# sercon.net
KiCad netlist of a schematic drawn in EAGLE
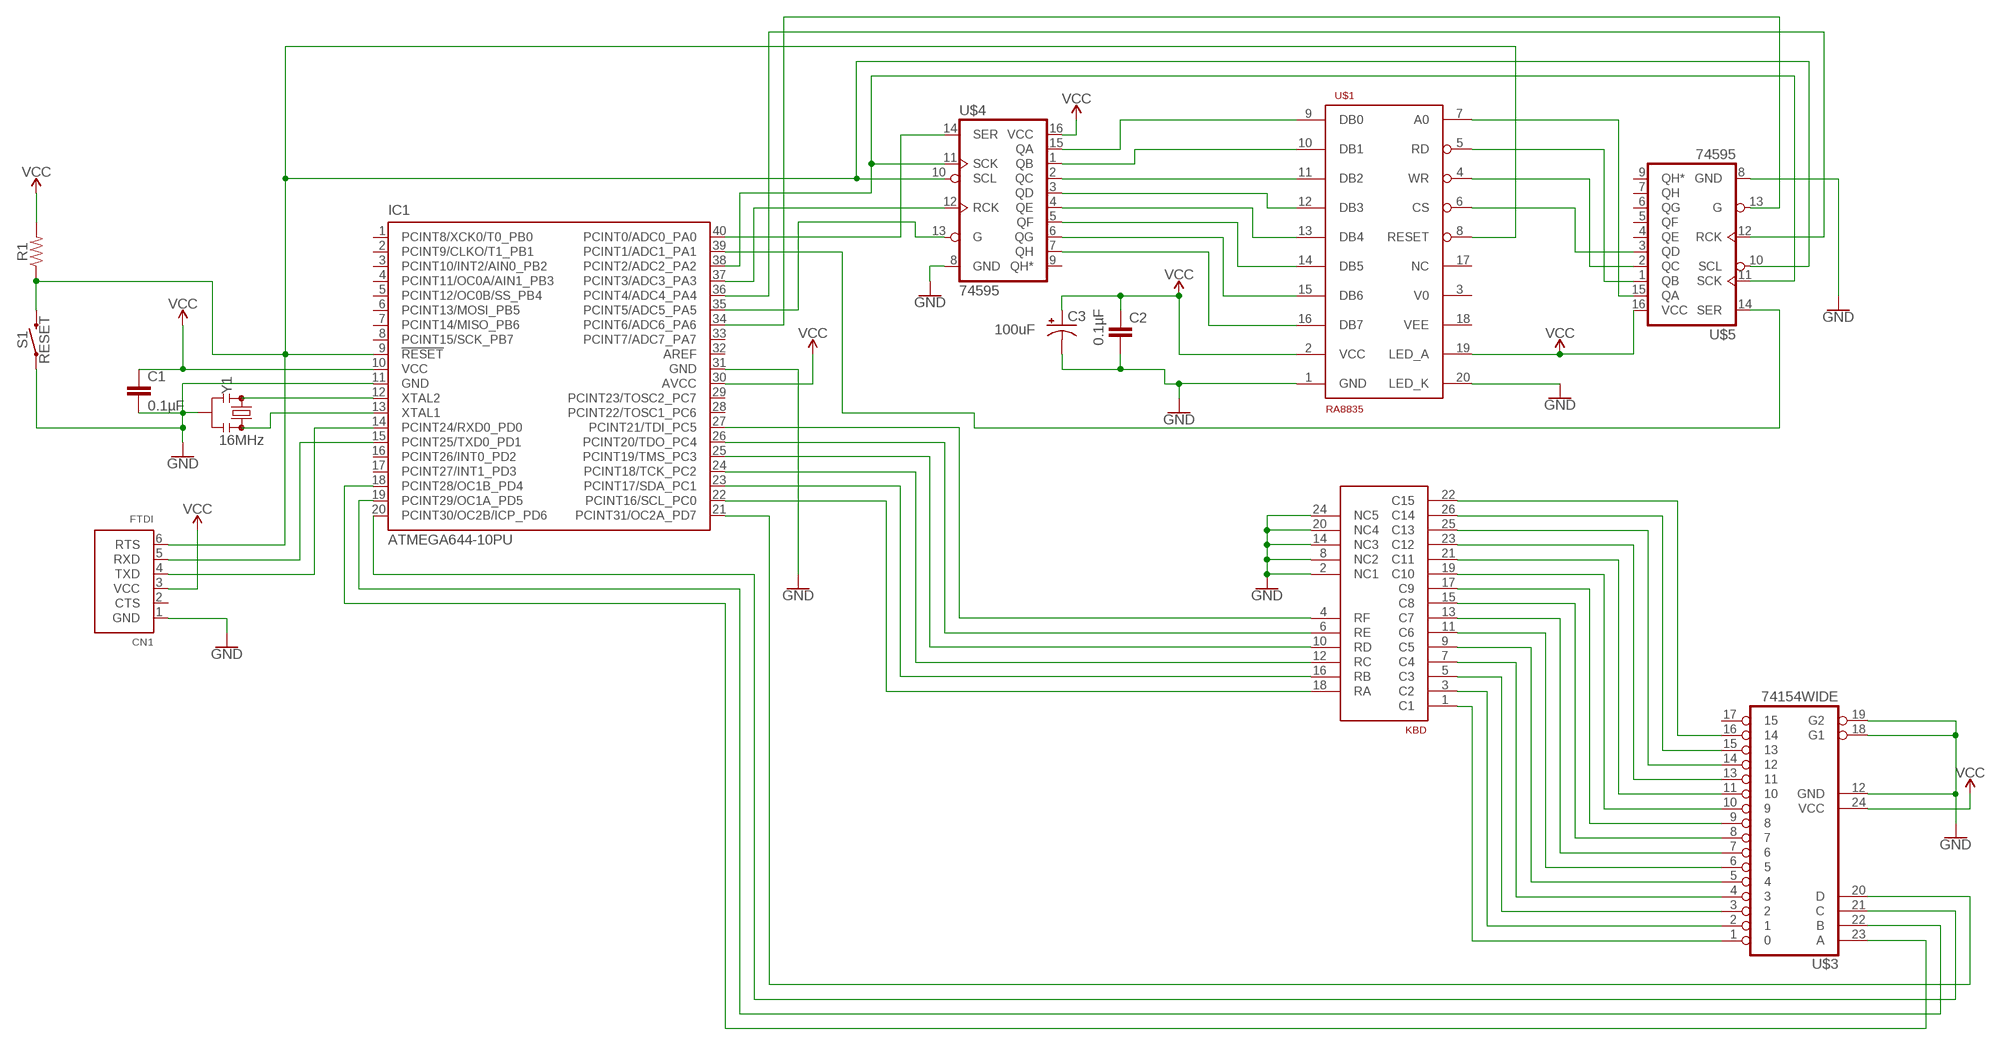
[diagram p0: schematic, sheet 1]

(export (version "E")
  (design (tool "Eeschema 10.0.6"))
  (components
    (comp (ref "C1")
      (value "0.1µF")
      (footprint "eagle-import:C2.5-3")
      (libsource (lib "eagle-import") (part "C2,5-3"))
    )
    (comp (ref "C2")
      (value "0.1µF")
      (footprint "eagle-import:C2.5-3")
      (libsource (lib "eagle-import") (part "C2,5-3"))
    )
    (comp (ref "C3")
      (value "100uF")
      (footprint "eagle-import:CPOL-RADIAL-2.5MM-6.5MM")
      (libsource (lib "eagle-import") (part "100UF-POLAR-RADIAL-2.5MM-25V-20%"))
    )
    (comp (ref "CN1")
      (value "FTDI")
      (footprint "eagle-import:1X06_ROUND")
      (libsource (lib "eagle-import") (part "FTDIUSBCABLE"))
    )
    (comp (ref "IC1")
      (value "ATMEGA644-10PU")
      (footprint "eagle-import:DIL40")
      (fields (field (name "MPN") "ATMEGA644V-10PU"))
      (libsource (lib "eagle-import") (part "ATMEGA644-PU10"))
    )
    (comp (ref "R1")
      (value "RESISTORAXIAL-0.3")
      (footprint "eagle-import:AXIAL-0.3")
      (libsource (lib "eagle-import") (part "RESISTORAXIAL-0.3"))
    )
    (comp (ref "S1")
      (value "RESET")
      (footprint "eagle-import:TACTILE_SWITCH_PTH_6.0MM")
      (libsource (lib "eagle-import") (part "MOMENTARY-SWITCH-SPST-PTH-6.0MM"))
    )
    (comp (ref "U$1")
      (value "RA8835")
      (footprint "eagle-import:2X10")
      (libsource (lib "eagle-import") (part "RA8835"))
    )
    (comp (ref "U$2")
      (value "5140KBD")
      (footprint "eagle-import:2X13")
      (libsource (lib "eagle-import") (part "5140KBD"))
    )
    (comp (ref "U$3")
      (value "74154WIDE")
      (footprint "eagle-import:DIL24-6")
      (libsource (lib "eagle-import") (part "74154WIDE"))
    )
    (comp (ref "U$4")
      (value "74595")
      (footprint "eagle-import:DIL16")
      (libsource (lib "eagle-import") (part "74595"))
    )
    (comp (ref "U$5")
      (value "74595")
      (footprint "eagle-import:DIL16")
      (libsource (lib "eagle-import") (part "74595"))
    )
    (comp (ref "Y1")
      (value "16MHz")
      (footprint "eagle-import:RESONATOR-PTH-7.6X3.8")
      (libsource (lib "eagle-import") (part "RESONATORPTH-7.6X3.8"))
    )
  )
  (nets
    (net (code "1") (name "GND") (class "Default")
      (node (ref "C1") (pin "2") (pinfunction "2_2") (pintype "passive"))
      (node (ref "C2") (pin "2") (pinfunction "2_2") (pintype "passive"))
      (node (ref "C3") (pin "2") (pinfunction "-_2") (pintype "passive"))
      (node (ref "CN1") (pin "1") (pinfunction "GND_1") (pintype "bidirectional"))
      (node (ref "IC1") (pin "11") (pinfunction "GND_11") (pintype "power_in"))
      (node (ref "IC1") (pin "31") (pinfunction "GND_31") (pintype "power_in"))
      (node (ref "S1") (pin "1") (pinfunction "1_1") (pintype "passive"))
      (node (ref "U$1") (pin "1") (pinfunction "GND_1") (pintype "power_in"))
      (node (ref "U$1") (pin "20") (pinfunction "LED_K_20") (pintype "bidirectional"))
      (node (ref "U$2") (pin "14") (pinfunction "NC3_14") (pintype "bidirectional"))
      (node (ref "U$2") (pin "2") (pinfunction "NC1_2") (pintype "bidirectional"))
      (node (ref "U$2") (pin "20") (pinfunction "NC4_20") (pintype "bidirectional"))
      (node (ref "U$2") (pin "24") (pinfunction "NC5_24") (pintype "bidirectional"))
      (node (ref "U$2") (pin "8") (pinfunction "NC2_8") (pintype "bidirectional"))
      (node (ref "U$3") (pin "12") (pinfunction "GND_12") (pintype "power_in"))
      (node (ref "U$3") (pin "18") (pinfunction "G1_18") (pintype "input"))
      (node (ref "U$3") (pin "19") (pinfunction "G2_19") (pintype "input"))
      (node (ref "U$4") (pin "8") (pinfunction "GND_8") (pintype "power_in"))
      (node (ref "U$5") (pin "8") (pinfunction "GND_8") (pintype "power_in"))
      (node (ref "Y1") (pin "2") (pinfunction "2_2") (pintype "passive"))
    )
    (net (code "2") (name "Net-(CN1-RTS)") (class "Default")
      (node (ref "CN1") (pin "6") (pinfunction "RTS_6") (pintype "bidirectional"))
      (node (ref "IC1") (pin "9") (pinfunction "~{RESET}_9") (pintype "input"))
      (node (ref "R1") (pin "P$1") (pinfunction "1_P$1") (pintype "passive"))
      (node (ref "S1") (pin "3") (pinfunction "2_3") (pintype "passive"))
      (node (ref "U$1") (pin "8") (pinfunction "RESET_8") (pintype "input"))
      (node (ref "U$4") (pin "10") (pinfunction "SCL_10") (pintype "input"))
      (node (ref "U$5") (pin "10") (pinfunction "SCL_10") (pintype "input"))
    )
    (net (code "3") (name "Net-(CN1-RXD)") (class "Default")
      (node (ref "CN1") (pin "5") (pinfunction "RXD_5") (pintype "bidirectional"))
      (node (ref "IC1") (pin "15") (pinfunction "PCINT25/TXD0_PD1_15") (pintype "bidirectional"))
    )
    (net (code "4") (name "Net-(CN1-TXD)") (class "Default")
      (node (ref "CN1") (pin "4") (pinfunction "TXD_4") (pintype "bidirectional"))
      (node (ref "IC1") (pin "14") (pinfunction "PCINT24/RXD0_PD0_14") (pintype "bidirectional"))
    )
    (net (code "5") (name "Net-(IC1-PCINT0{slash}ADC0_PA0)") (class "Default")
      (node (ref "IC1") (pin "40") (pinfunction "PCINT0/ADC0_PA0_40") (pintype "bidirectional"))
      (node (ref "U$4") (pin "14") (pinfunction "SER_14") (pintype "input"))
    )
    (net (code "6") (name "Net-(IC1-PCINT1{slash}ADC1_PA1)") (class "Default")
      (node (ref "IC1") (pin "39") (pinfunction "PCINT1/ADC1_PA1_39") (pintype "bidirectional"))
      (node (ref "U$5") (pin "14") (pinfunction "SER_14") (pintype "input"))
    )
    (net (code "7") (name "Net-(IC1-PCINT2{slash}ADC2_PA2)") (class "Default")
      (node (ref "IC1") (pin "38") (pinfunction "PCINT2/ADC2_PA2_38") (pintype "bidirectional"))
      (node (ref "U$4") (pin "11") (pinfunction "SCK_11") (pintype "input"))
      (node (ref "U$5") (pin "11") (pinfunction "SCK_11") (pintype "input"))
    )
    (net (code "8") (name "Net-(IC1-PCINT3{slash}ADC3_PA3)") (class "Default")
      (node (ref "IC1") (pin "37") (pinfunction "PCINT3/ADC3_PA3_37") (pintype "bidirectional"))
      (node (ref "U$4") (pin "12") (pinfunction "RCK_12") (pintype "input"))
    )
    (net (code "9") (name "Net-(IC1-PCINT4{slash}ADC4_PA4)") (class "Default")
      (node (ref "IC1") (pin "36") (pinfunction "PCINT4/ADC4_PA4_36") (pintype "bidirectional"))
      (node (ref "U$5") (pin "12") (pinfunction "RCK_12") (pintype "input"))
    )
    (net (code "10") (name "Net-(IC1-PCINT5{slash}ADC5_PA5)") (class "Default")
      (node (ref "IC1") (pin "35") (pinfunction "PCINT5/ADC5_PA5_35") (pintype "bidirectional"))
      (node (ref "U$4") (pin "13") (pinfunction "G_13") (pintype "input"))
    )
    (net (code "11") (name "Net-(IC1-PCINT6{slash}ADC6_PA6)") (class "Default")
      (node (ref "IC1") (pin "34") (pinfunction "PCINT6/ADC6_PA6_34") (pintype "bidirectional"))
      (node (ref "U$5") (pin "13") (pinfunction "G_13") (pintype "input"))
    )
    (net (code "12") (name "Net-(IC1-PCINT16{slash}SCL_PC0)") (class "Default")
      (node (ref "IC1") (pin "22") (pinfunction "PCINT16/SCL_PC0_22") (pintype "bidirectional"))
      (node (ref "U$2") (pin "18") (pinfunction "RA_18") (pintype "bidirectional"))
    )
    (net (code "13") (name "Net-(IC1-PCINT17{slash}SDA_PC1)") (class "Default")
      (node (ref "IC1") (pin "23") (pinfunction "PCINT17/SDA_PC1_23") (pintype "bidirectional"))
      (node (ref "U$2") (pin "16") (pinfunction "RB_16") (pintype "bidirectional"))
    )
    (net (code "14") (name "Net-(IC1-PCINT18{slash}TCK_PC2)") (class "Default")
      (node (ref "IC1") (pin "24") (pinfunction "PCINT18/TCK_PC2_24") (pintype "bidirectional"))
      (node (ref "U$2") (pin "12") (pinfunction "RC_12") (pintype "bidirectional"))
    )
    (net (code "15") (name "Net-(IC1-PCINT19{slash}TMS_PC3)") (class "Default")
      (node (ref "IC1") (pin "25") (pinfunction "PCINT19/TMS_PC3_25") (pintype "bidirectional"))
      (node (ref "U$2") (pin "10") (pinfunction "RD_10") (pintype "bidirectional"))
    )
    (net (code "16") (name "Net-(IC1-PCINT20{slash}TDO_PC4)") (class "Default")
      (node (ref "IC1") (pin "26") (pinfunction "PCINT20/TDO_PC4_26") (pintype "bidirectional"))
      (node (ref "U$2") (pin "6") (pinfunction "RE_6") (pintype "bidirectional"))
    )
    (net (code "17") (name "Net-(IC1-PCINT21{slash}TDI_PC5)") (class "Default")
      (node (ref "IC1") (pin "27") (pinfunction "PCINT21/TDI_PC5_27") (pintype "bidirectional"))
      (node (ref "U$2") (pin "4") (pinfunction "RF_4") (pintype "bidirectional"))
    )
    (net (code "18") (name "Net-(IC1-PCINT28{slash}OC1B_PD4)") (class "Default")
      (node (ref "IC1") (pin "18") (pinfunction "PCINT28/OC1B_PD4_18") (pintype "bidirectional"))
      (node (ref "U$3") (pin "23") (pinfunction "A_23") (pintype "input"))
    )
    (net (code "19") (name "Net-(IC1-PCINT29{slash}OC1A_PD5)") (class "Default")
      (node (ref "IC1") (pin "19") (pinfunction "PCINT29/OC1A_PD5_19") (pintype "bidirectional"))
      (node (ref "U$3") (pin "22") (pinfunction "B_22") (pintype "input"))
    )
    (net (code "20") (name "Net-(IC1-PCINT30{slash}OC2B{slash}ICP_PD6)") (class "Default")
      (node (ref "IC1") (pin "20") (pinfunction "PCINT30/OC2B/ICP_PD6_20") (pintype "bidirectional"))
      (node (ref "U$3") (pin "21") (pinfunction "C_21") (pintype "input"))
    )
    (net (code "21") (name "Net-(IC1-PCINT31{slash}OC2A_PD7)") (class "Default")
      (node (ref "IC1") (pin "21") (pinfunction "PCINT31/OC2A_PD7_21") (pintype "bidirectional"))
      (node (ref "U$3") (pin "20") (pinfunction "D_20") (pintype "input"))
    )
    (net (code "22") (name "Net-(IC1-XTAL1)") (class "Default")
      (node (ref "IC1") (pin "13") (pinfunction "XTAL1_13") (pintype "input"))
      (node (ref "Y1") (pin "3") (pinfunction "3_3") (pintype "passive"))
    )
    (net (code "23") (name "Net-(IC1-XTAL2)") (class "Default")
      (node (ref "IC1") (pin "12") (pinfunction "XTAL2_12") (pintype "output"))
      (node (ref "Y1") (pin "1") (pinfunction "1_1") (pintype "passive"))
    )
    (net (code "24") (name "Net-(U$1-A0)") (class "Default")
      (node (ref "U$1") (pin "7") (pinfunction "A0_7") (pintype "input"))
      (node (ref "U$5") (pin "15") (pinfunction "QA_15") (pintype "tri_state"))
    )
    (net (code "25") (name "Net-(U$1-CS)") (class "Default")
      (node (ref "U$1") (pin "6") (pinfunction "CS_6") (pintype "input"))
      (node (ref "U$5") (pin "3") (pinfunction "QD_3") (pintype "tri_state"))
    )
    (net (code "26") (name "Net-(U$1-DB0)") (class "Default")
      (node (ref "U$1") (pin "9") (pinfunction "DB0_9") (pintype "bidirectional"))
      (node (ref "U$4") (pin "15") (pinfunction "QA_15") (pintype "tri_state"))
    )
    (net (code "27") (name "Net-(U$1-DB1)") (class "Default")
      (node (ref "U$1") (pin "10") (pinfunction "DB1_10") (pintype "bidirectional"))
      (node (ref "U$4") (pin "1") (pinfunction "QB_1") (pintype "tri_state"))
    )
    (net (code "28") (name "Net-(U$1-DB2)") (class "Default")
      (node (ref "U$1") (pin "11") (pinfunction "DB2_11") (pintype "bidirectional"))
      (node (ref "U$4") (pin "2") (pinfunction "QC_2") (pintype "tri_state"))
    )
    (net (code "29") (name "Net-(U$1-DB3)") (class "Default")
      (node (ref "U$1") (pin "12") (pinfunction "DB3_12") (pintype "bidirectional"))
      (node (ref "U$4") (pin "3") (pinfunction "QD_3") (pintype "tri_state"))
    )
    (net (code "30") (name "Net-(U$1-DB4)") (class "Default")
      (node (ref "U$1") (pin "13") (pinfunction "DB4_13") (pintype "bidirectional"))
      (node (ref "U$4") (pin "4") (pinfunction "QE_4") (pintype "tri_state"))
    )
    (net (code "31") (name "Net-(U$1-DB5)") (class "Default")
      (node (ref "U$1") (pin "14") (pinfunction "DB5_14") (pintype "bidirectional"))
      (node (ref "U$4") (pin "5") (pinfunction "QF_5") (pintype "tri_state"))
    )
    (net (code "32") (name "Net-(U$1-DB6)") (class "Default")
      (node (ref "U$1") (pin "15") (pinfunction "DB6_15") (pintype "bidirectional"))
      (node (ref "U$4") (pin "6") (pinfunction "QG_6") (pintype "tri_state"))
    )
    (net (code "33") (name "Net-(U$1-DB7)") (class "Default")
      (node (ref "U$1") (pin "16") (pinfunction "DB7_16") (pintype "bidirectional"))
      (node (ref "U$4") (pin "7") (pinfunction "QH_7") (pintype "tri_state"))
    )
    (net (code "34") (name "Net-(U$1-RD)") (class "Default")
      (node (ref "U$1") (pin "5") (pinfunction "RD_5") (pintype "input"))
      (node (ref "U$5") (pin "1") (pinfunction "QB_1") (pintype "tri_state"))
    )
    (net (code "35") (name "Net-(U$1-WR)") (class "Default")
      (node (ref "U$1") (pin "4") (pinfunction "WR_4") (pintype "input"))
      (node (ref "U$5") (pin "2") (pinfunction "QC_2") (pintype "tri_state"))
    )
    (net (code "36") (name "Net-(U$2-C1)") (class "Default")
      (node (ref "U$2") (pin "1") (pinfunction "C1_1") (pintype "bidirectional"))
      (node (ref "U$3") (pin "1") (pinfunction "0_1") (pintype "output"))
    )
    (net (code "37") (name "Net-(U$2-C2)") (class "Default")
      (node (ref "U$2") (pin "3") (pinfunction "C2_3") (pintype "bidirectional"))
      (node (ref "U$3") (pin "2") (pinfunction "1_2") (pintype "output"))
    )
    (net (code "38") (name "Net-(U$2-C3)") (class "Default")
      (node (ref "U$2") (pin "5") (pinfunction "C3_5") (pintype "bidirectional"))
      (node (ref "U$3") (pin "3") (pinfunction "2_3") (pintype "output"))
    )
    (net (code "39") (name "Net-(U$2-C4)") (class "Default")
      (node (ref "U$2") (pin "7") (pinfunction "C4_7") (pintype "bidirectional"))
      (node (ref "U$3") (pin "4") (pinfunction "3_4") (pintype "output"))
    )
    (net (code "40") (name "Net-(U$2-C5)") (class "Default")
      (node (ref "U$2") (pin "9") (pinfunction "C5_9") (pintype "bidirectional"))
      (node (ref "U$3") (pin "5") (pinfunction "4_5") (pintype "output"))
    )
    (net (code "41") (name "Net-(U$2-C6)") (class "Default")
      (node (ref "U$2") (pin "11") (pinfunction "C6_11") (pintype "bidirectional"))
      (node (ref "U$3") (pin "6") (pinfunction "5_6") (pintype "output"))
    )
    (net (code "42") (name "Net-(U$2-C7)") (class "Default")
      (node (ref "U$2") (pin "13") (pinfunction "C7_13") (pintype "bidirectional"))
      (node (ref "U$3") (pin "7") (pinfunction "6_7") (pintype "output"))
    )
    (net (code "43") (name "Net-(U$2-C8)") (class "Default")
      (node (ref "U$2") (pin "15") (pinfunction "C8_15") (pintype "bidirectional"))
      (node (ref "U$3") (pin "8") (pinfunction "7_8") (pintype "output"))
    )
    (net (code "44") (name "Net-(U$2-C9)") (class "Default")
      (node (ref "U$2") (pin "17") (pinfunction "C9_17") (pintype "bidirectional"))
      (node (ref "U$3") (pin "9") (pinfunction "8_9") (pintype "output"))
    )
    (net (code "45") (name "Net-(U$2-C10)") (class "Default")
      (node (ref "U$2") (pin "19") (pinfunction "C10_19") (pintype "bidirectional"))
      (node (ref "U$3") (pin "10") (pinfunction "9_10") (pintype "output"))
    )
    (net (code "46") (name "Net-(U$2-C11)") (class "Default")
      (node (ref "U$2") (pin "21") (pinfunction "C11_21") (pintype "bidirectional"))
      (node (ref "U$3") (pin "11") (pinfunction "10_11") (pintype "output"))
    )
    (net (code "47") (name "Net-(U$2-C12)") (class "Default")
      (node (ref "U$2") (pin "23") (pinfunction "C12_23") (pintype "bidirectional"))
      (node (ref "U$3") (pin "13") (pinfunction "11_13") (pintype "output"))
    )
    (net (code "48") (name "Net-(U$2-C13)") (class "Default")
      (node (ref "U$2") (pin "25") (pinfunction "C13_25") (pintype "bidirectional"))
      (node (ref "U$3") (pin "14") (pinfunction "12_14") (pintype "output"))
    )
    (net (code "49") (name "Net-(U$2-C14)") (class "Default")
      (node (ref "U$2") (pin "26") (pinfunction "C14_26") (pintype "bidirectional"))
      (node (ref "U$3") (pin "15") (pinfunction "13_15") (pintype "output"))
    )
    (net (code "50") (name "Net-(U$2-C15)") (class "Default")
      (node (ref "U$2") (pin "22") (pinfunction "C15_22") (pintype "bidirectional"))
      (node (ref "U$3") (pin "16") (pinfunction "14_16") (pintype "output"))
    )
    (net (code "51") (name "VCC") (class "Default")
      (node (ref "C1") (pin "1") (pinfunction "1_1") (pintype "passive"))
      (node (ref "C2") (pin "1") (pinfunction "1_1") (pintype "passive"))
      (node (ref "C3") (pin "1") (pinfunction "+_1") (pintype "passive"))
      (node (ref "CN1") (pin "3") (pinfunction "VCC_3") (pintype "bidirectional"))
      (node (ref "IC1") (pin "10") (pinfunction "VCC_10") (pintype "power_in"))
      (node (ref "IC1") (pin "30") (pinfunction "AVCC_30") (pintype "power_in"))
      (node (ref "R1") (pin "P$2") (pinfunction "2_P$2") (pintype "passive"))
      (node (ref "U$1") (pin "19") (pinfunction "LED_A_19") (pintype "bidirectional"))
      (node (ref "U$1") (pin "2") (pinfunction "VCC_2") (pintype "power_in"))
      (node (ref "U$3") (pin "24") (pinfunction "VCC_24") (pintype "power_in"))
      (node (ref "U$4") (pin "16") (pinfunction "VCC_16") (pintype "power_in"))
      (node (ref "U$5") (pin "16") (pinfunction "VCC_16") (pintype "power_in"))
    )
    (net (code "52") (name "unconnected-(CN1-CTS-Pad2)") (class "Default")
      (node (ref "CN1") (pin "2") (pinfunction "CTS_2") (pintype "bidirectional"))
    )
    (net (code "53") (name "unconnected-(IC1-AREF-Pad32)") (class "Default")
      (node (ref "IC1") (pin "32") (pinfunction "AREF_32") (pintype "passive"))
    )
    (net (code "54") (name "unconnected-(IC1-PCINT7{slash}ADC7_PA7-Pad33)") (class "Default")
      (node (ref "IC1") (pin "33") (pinfunction "PCINT7/ADC7_PA7_33") (pintype "bidirectional"))
    )
    (net (code "55") (name "unconnected-(IC1-PCINT8{slash}XCK0{slash}T0_PB0-Pad1)") (class "Default")
      (node (ref "IC1") (pin "1") (pinfunction "PCINT8/XCK0/T0_PB0_1") (pintype "bidirectional"))
    )
    (net (code "56") (name "unconnected-(IC1-PCINT9{slash}CLKO{slash}T1_PB1-Pad2)") (class "Default")
      (node (ref "IC1") (pin "2") (pinfunction "PCINT9/CLKO/T1_PB1_2") (pintype "bidirectional"))
    )
    (net (code "57") (name "unconnected-(IC1-PCINT10{slash}INT2{slash}AIN0_PB2-Pad3)") (class "Default")
      (node (ref "IC1") (pin "3") (pinfunction "PCINT10/INT2/AIN0_PB2_3") (pintype "bidirectional"))
    )
    (net (code "58") (name "unconnected-(IC1-PCINT11{slash}OC0A{slash}AIN1_PB3-Pad4)") (class "Default")
      (node (ref "IC1") (pin "4") (pinfunction "PCINT11/OC0A/AIN1_PB3_4") (pintype "bidirectional"))
    )
    (net (code "59") (name "unconnected-(IC1-PCINT12{slash}OC0B{slash}SS_PB4-Pad5)") (class "Default")
      (node (ref "IC1") (pin "5") (pinfunction "PCINT12/OC0B/SS_PB4_5") (pintype "bidirectional"))
    )
    (net (code "60") (name "unconnected-(IC1-PCINT13{slash}MOSI_PB5-Pad6)") (class "Default")
      (node (ref "IC1") (pin "6") (pinfunction "PCINT13/MOSI_PB5_6") (pintype "bidirectional"))
    )
    (net (code "61") (name "unconnected-(IC1-PCINT14{slash}MISO_PB6-Pad7)") (class "Default")
      (node (ref "IC1") (pin "7") (pinfunction "PCINT14/MISO_PB6_7") (pintype "bidirectional"))
    )
    (net (code "62") (name "unconnected-(IC1-PCINT15{slash}SCK_PB7-Pad8)") (class "Default")
      (node (ref "IC1") (pin "8") (pinfunction "PCINT15/SCK_PB7_8") (pintype "bidirectional"))
    )
    (net (code "63") (name "unconnected-(IC1-PCINT22{slash}TOSC1_PC6-Pad28)") (class "Default")
      (node (ref "IC1") (pin "28") (pinfunction "PCINT22/TOSC1_PC6_28") (pintype "bidirectional"))
    )
    (net (code "64") (name "unconnected-(IC1-PCINT23{slash}TOSC2_PC7-Pad29)") (class "Default")
      (node (ref "IC1") (pin "29") (pinfunction "PCINT23/TOSC2_PC7_29") (pintype "bidirectional"))
    )
    (net (code "65") (name "unconnected-(IC1-PCINT26{slash}INT0_PD2-Pad16)") (class "Default")
      (node (ref "IC1") (pin "16") (pinfunction "PCINT26/INT0_PD2_16") (pintype "bidirectional"))
    )
    (net (code "66") (name "unconnected-(IC1-PCINT27{slash}INT1_PD3-Pad17)") (class "Default")
      (node (ref "IC1") (pin "17") (pinfunction "PCINT27/INT1_PD3_17") (pintype "bidirectional"))
    )
    (net (code "67") (name "unconnected-(U$1-NC-Pad17)") (class "Default")
      (node (ref "U$1") (pin "17") (pinfunction "NC_17") (pintype "no_connect"))
    )
    (net (code "68") (name "unconnected-(U$1-V0-Pad3)") (class "Default")
      (node (ref "U$1") (pin "3") (pinfunction "V0_3") (pintype "bidirectional"))
    )
    (net (code "69") (name "unconnected-(U$1-VEE-Pad18)") (class "Default")
      (node (ref "U$1") (pin "18") (pinfunction "VEE_18") (pintype "bidirectional"))
    )
    (net (code "70") (name "unconnected-(U$3-15-Pad17)") (class "Default")
      (node (ref "U$3") (pin "17") (pinfunction "15_17") (pintype "output"))
    )
    (net (code "71") (name "unconnected-(U$4-QH*-Pad9)") (class "Default")
      (node (ref "U$4") (pin "9") (pinfunction "QH*_9") (pintype "tri_state"))
    )
    (net (code "72") (name "unconnected-(U$5-QE-Pad4)") (class "Default")
      (node (ref "U$5") (pin "4") (pinfunction "QE_4") (pintype "tri_state"))
    )
    (net (code "73") (name "unconnected-(U$5-QF-Pad5)") (class "Default")
      (node (ref "U$5") (pin "5") (pinfunction "QF_5") (pintype "tri_state"))
    )
    (net (code "74") (name "unconnected-(U$5-QG-Pad6)") (class "Default")
      (node (ref "U$5") (pin "6") (pinfunction "QG_6") (pintype "tri_state"))
    )
    (net (code "75") (name "unconnected-(U$5-QH*-Pad9)") (class "Default")
      (node (ref "U$5") (pin "9") (pinfunction "QH*_9") (pintype "tri_state"))
    )
    (net (code "76") (name "unconnected-(U$5-QH-Pad7)") (class "Default")
      (node (ref "U$5") (pin "7") (pinfunction "QH_7") (pintype "tri_state"))
    )
  )
)
